# 0_66_oled.net
KiCad netlist of a schematic drawn in Altium Designer
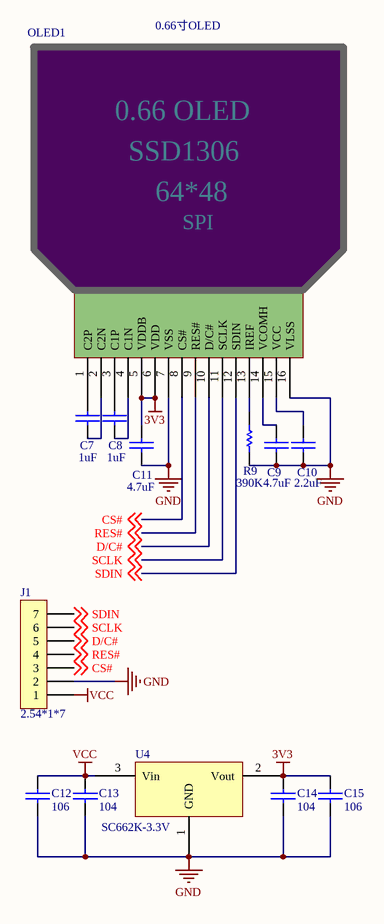
[diagram p0: 0.66寸oled.SchDoc]

(export (version "E")
  (design (tool "Eeschema 10.0.6"))
  (components
    (comp (ref "C7")
      (value "1uF")
      (footprint "0603-C")
      (description "无极性电容")
      (libsource (lib "电容") (part "CAP"))
    )
    (comp (ref "C8")
      (value "1uF")
      (footprint "0603-C")
      (description "无极性电容")
      (libsource (lib "电容") (part "CAP"))
    )
    (comp (ref "C9")
      (value "4.7uF")
      (footprint "0603-C")
      (description "无极性电容")
      (libsource (lib "电容") (part "CAP"))
    )
    (comp (ref "C10")
      (value "2.2uF")
      (footprint "0603-C")
      (description "无极性电容")
      (libsource (lib "电容") (part "CAP"))
    )
    (comp (ref "C11")
      (value "4.7uF")
      (footprint "0603-C")
      (description "无极性电容")
      (libsource (lib "电容") (part "CAP"))
    )
    (comp (ref "C12")
      (value "106")
      (footprint "0603-C")
      (description "无极性电容")
      (libsource (lib "电容") (part "CAP"))
    )
    (comp (ref "C13")
      (value "104")
      (footprint "0603-C")
      (description "无极性电容")
      (libsource (lib "电容") (part "CAP"))
    )
    (comp (ref "C14")
      (value "104")
      (footprint "0603-C")
      (description "无极性电容")
      (libsource (lib "电容") (part "CAP"))
    )
    (comp (ref "C15")
      (value "106")
      (footprint "0603-C")
      (description "无极性电容")
      (libsource (lib "电容") (part "CAP"))
    )
    (comp (ref "J1")
      (value "2.54*1*7")
      (footprint "Pin HDR1X7/2.54mm-S")
      (libsource (lib "排针") (part "Pin HDR1X7"))
    )
    (comp (ref "OLED1")
      (value "0.66寸OLED")
      (footprint "0.66OLED-W")
      (libsource (lib "点焊机") (part "0.66寸OLED"))
    )
    (comp (ref "R9") (value "390K") (footprint "0603-R") (libsource (lib "电阻") (part "RES")))
    (comp (ref "U4")
      (value "SC662K-3.3V")
      (footprint "SOT-23")
      (description "三端稳压芯片")
      (libsource (lib "电源芯片") (part "AMS1117"))
    )
  )
  (nets
    (net (code "1") (name "3V3") (class "Default")
      (node (ref "C11") (pin "2") (pinfunction "2_2") (pintype "passive"))
      (node (ref "C14") (pin "1") (pinfunction "1_1") (pintype "passive"))
      (node (ref "C15") (pin "1") (pinfunction "1_1") (pintype "passive"))
      (node (ref "OLED1") (pin "5") (pinfunction "VDDB_5") (pintype "passive"))
      (node (ref "OLED1") (pin "6") (pinfunction "VDD_6") (pintype "passive"))
      (node (ref "U4") (pin "2") (pinfunction "Vout_2") (pintype "passive"))
    )
    (net (code "2") (name "CS#") (class "Default")
      (node (ref "J1") (pin "3") (pinfunction "3_3") (pintype "passive"))
      (node (ref "OLED1") (pin "8") (pinfunction "CS#_8") (pintype "passive"))
    )
    (net (code "3") (name "D{slash}C#") (class "Default")
      (node (ref "J1") (pin "5") (pinfunction "5_5") (pintype "passive"))
      (node (ref "OLED1") (pin "10") (pinfunction "D/C#_10") (pintype "passive"))
    )
    (net (code "4") (name "GND") (class "Default")
      (node (ref "C10") (pin "1") (pinfunction "1_1") (pintype "passive"))
      (node (ref "C11") (pin "1") (pinfunction "1_1") (pintype "passive"))
      (node (ref "C12") (pin "2") (pinfunction "2_2") (pintype "passive"))
      (node (ref "C13") (pin "2") (pinfunction "2_2") (pintype "passive"))
      (node (ref "C14") (pin "2") (pinfunction "2_2") (pintype "passive"))
      (node (ref "C15") (pin "2") (pinfunction "2_2") (pintype "passive"))
      (node (ref "C9") (pin "1") (pinfunction "1_1") (pintype "passive"))
      (node (ref "J1") (pin "2") (pinfunction "2_2") (pintype "passive"))
      (node (ref "OLED1") (pin "16") (pinfunction "VLSS_16") (pintype "passive"))
      (node (ref "OLED1") (pin "7") (pinfunction "VSS_7") (pintype "passive"))
      (node (ref "R9") (pin "2") (pinfunction "2_2") (pintype "passive"))
      (node (ref "U4") (pin "1") (pinfunction "GND_1") (pintype "passive"))
    )
    (net (code "5") (name "Net-(OLED1-C1N)") (class "Default")
      (node (ref "C8") (pin "1") (pinfunction "1_1") (pintype "passive"))
      (node (ref "OLED1") (pin "4") (pinfunction "C1N_4") (pintype "passive"))
    )
    (net (code "6") (name "Net-(OLED1-C1P)") (class "Default")
      (node (ref "C8") (pin "2") (pinfunction "2_2") (pintype "passive"))
      (node (ref "OLED1") (pin "3") (pinfunction "C1P_3") (pintype "passive"))
    )
    (net (code "7") (name "Net-(OLED1-C2N)") (class "Default")
      (node (ref "C7") (pin "1") (pinfunction "1_1") (pintype "passive"))
      (node (ref "OLED1") (pin "2") (pinfunction "C2N_2") (pintype "passive"))
    )
    (net (code "8") (name "Net-(OLED1-C2P)") (class "Default")
      (node (ref "C7") (pin "2") (pinfunction "2_2") (pintype "passive"))
      (node (ref "OLED1") (pin "1") (pinfunction "C2P_1") (pintype "passive"))
    )
    (net (code "9") (name "Net-(OLED1-IREF)") (class "Default")
      (node (ref "OLED1") (pin "13") (pinfunction "IREF_13") (pintype "passive"))
      (node (ref "R9") (pin "1") (pinfunction "1_1") (pintype "passive"))
    )
    (net (code "10") (name "Net-(OLED1-VCC)") (class "Default")
      (node (ref "C10") (pin "2") (pinfunction "2_2") (pintype "passive"))
      (node (ref "OLED1") (pin "15") (pinfunction "VCC_15") (pintype "passive"))
    )
    (net (code "11") (name "Net-(OLED1-VCOMH)") (class "Default")
      (node (ref "C9") (pin "2") (pinfunction "2_2") (pintype "passive"))
      (node (ref "OLED1") (pin "14") (pinfunction "VCOMH_14") (pintype "passive"))
    )
    (net (code "12") (name "RES#") (class "Default")
      (node (ref "J1") (pin "4") (pinfunction "4_4") (pintype "passive"))
      (node (ref "OLED1") (pin "9") (pinfunction "RES#_9") (pintype "passive"))
    )
    (net (code "13") (name "SCLK") (class "Default")
      (node (ref "J1") (pin "6") (pinfunction "6_6") (pintype "passive"))
      (node (ref "OLED1") (pin "11") (pinfunction "SCLK_11") (pintype "passive"))
    )
    (net (code "14") (name "SDIN") (class "Default")
      (node (ref "J1") (pin "7") (pinfunction "7_7") (pintype "passive"))
      (node (ref "OLED1") (pin "12") (pinfunction "SDIN_12") (pintype "passive"))
    )
    (net (code "15") (name "VCC") (class "Default")
      (node (ref "C12") (pin "1") (pinfunction "1_1") (pintype "passive"))
      (node (ref "C13") (pin "1") (pinfunction "1_1") (pintype "passive"))
      (node (ref "J1") (pin "1") (pinfunction "1_1") (pintype "passive"))
      (node (ref "U4") (pin "3") (pinfunction "Vin_3") (pintype "passive"))
    )
  )
)
